# Interface.net
KiCad netlist of a schematic drawn in Altium Designer
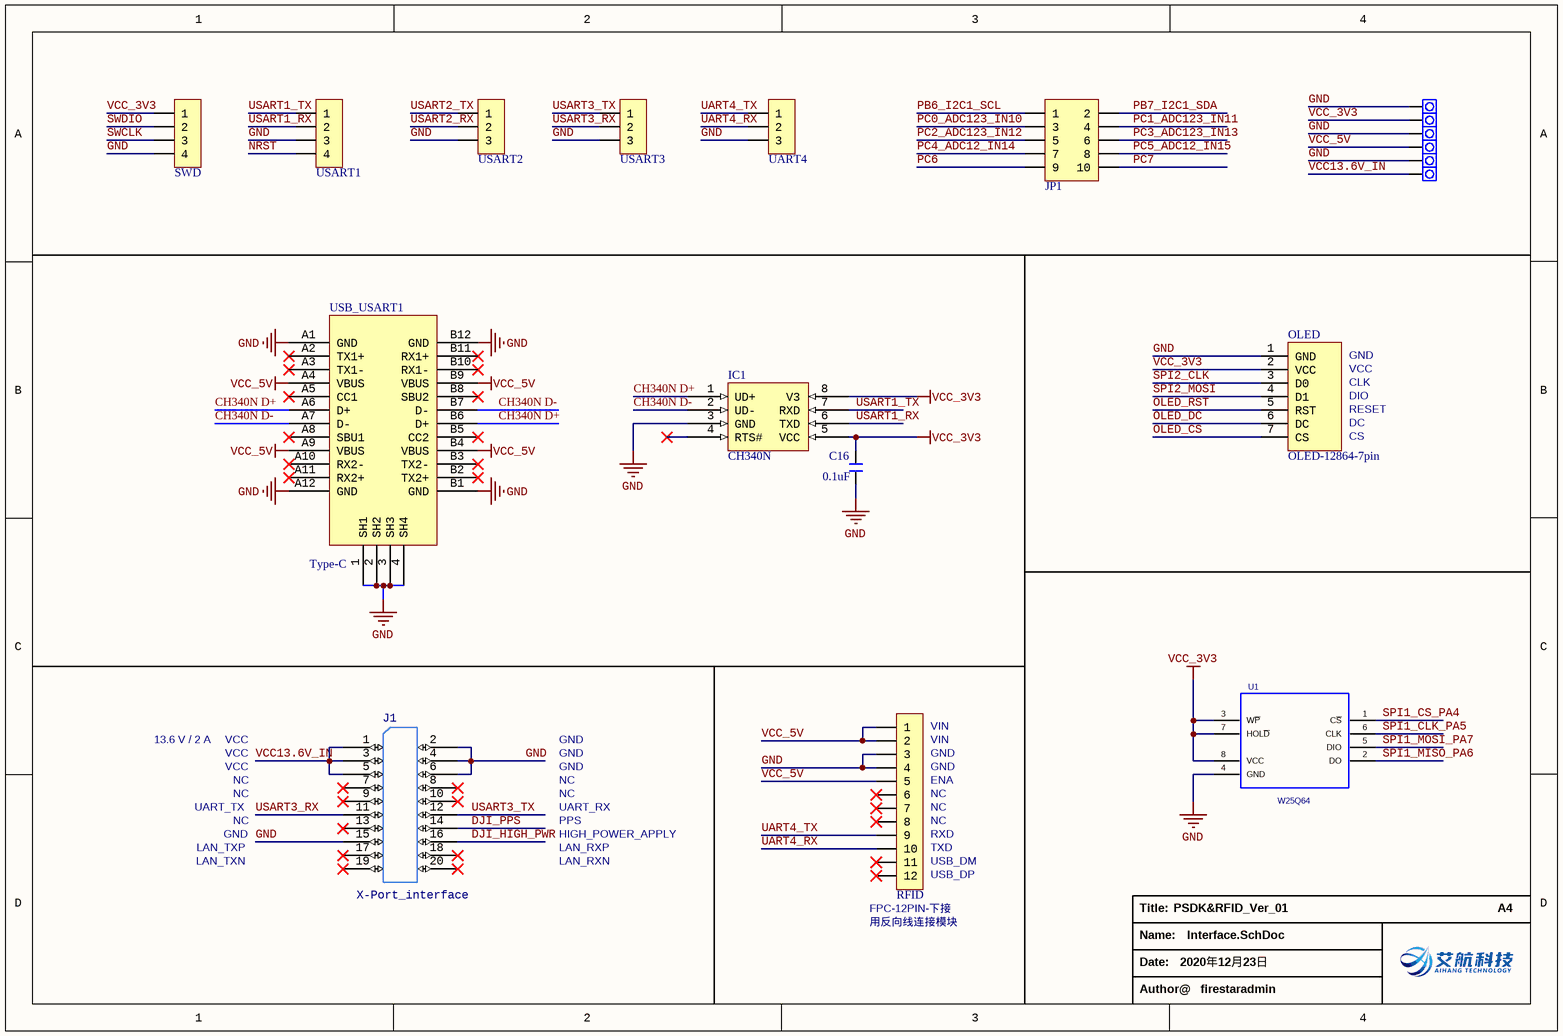
[diagram p0: Interface.SchDoc]

(export (version "E")
  (design (tool "Eeschema 10.0.6"))
  (components
    (comp (ref "C16")
      (value "0.1uF")
      (footprint "C 0603_L")
      (description "无极性贴片电容")
      (fields (field (name "版权归属") "源创客"))
      (libsource (lib "altium-import") (part "root_1_C_"))
    )
    (comp (ref "H1")
      (value "PAD")
      (footprint "PAD2-2.54")
      (description "引线焊盘")
      (fields (field (name "版权归属") "源创客"))
      (libsource (lib "SCH- 未分类器件") (part "PAD2"))
    )
    (comp (ref "H2")
      (value "PAD")
      (footprint "PAD2-2.54")
      (description "引线焊盘")
      (fields (field (name "版权归属") "源创客"))
      (libsource (lib "SCH- 未分类器件") (part "PAD2"))
    )
    (comp (ref "H3")
      (value "PAD")
      (footprint "PAD2-2.54")
      (description "引线焊盘")
      (fields (field (name "版权归属") "源创客"))
      (libsource (lib "SCH- 未分类器件") (part "PAD2"))
    )
    (comp (ref "IC1")
      (value "CH340N")
      (footprint "SOP8_N")
      (description "USB 转串口芯片 CH330/CH340N")
      (libsource (lib "altium-import") (part "root_0_CH340N_"))
    )
    (comp (ref "J1")
      (value "X-Port_interface")
      (footprint "s-50419-020xx-001")
      (description "20Pin-1.0MM-板对线连接器母座-WTB Wafer Conn.SMT D/R S/T Type.")
      (libsource (lib "SCH-板对线连接器-脚距1.0mm") (part "s-50419-020xx-001"))
    )
    (comp (ref "JP1")
      (value "Header 5X2")
      (footprint "HDR2.54-LI-2x5P")
      (description "5*2P接插件")
      (fields (field (name "版权归属") "源创客"))
      (libsource (lib "SCH-接插件-脚距2.54") (part "Header 5X2"))
    )
    (comp (ref "OLED")
      (value "OLED-12864-7pin")
      (footprint "OLED 0.96-7Pin")
      (description "OLED显示屏12864液晶屏串口oled模块ssd1306 12864OLED屏")
      (fields (field (name "版权归属") "源创客"))
      (libsource (lib "SCH-显示器件") (part "OLED-7pin-128x64-模组"))
    )
    (comp (ref "RFID")
      (value "FPC1.0-12P")
      (footprint "FPC1.0-2H-WS-12P")
      (description "FPC连接器")
      (fields (field (name "版权归属") "源创客"))
      (libsource (lib "SCH- FPC连接器") (part "FPC-12P"))
    )
    (comp (ref "SWD")
      (value "HDR-1X4")
      (footprint "HDR2.54-LI-4P")
      (description "4P接插件")
      (fields (field (name "版权归属") "源创客"))
      (libsource (lib "SCH-接插件-脚距2.54") (part "Header 4"))
    )
    (comp (ref "U1")
      (value "W25Q64")
      (footprint "SOP8W_L")
      (libsource (lib "altium-import") (part "root_0_W25Q64_"))
    )
    (comp (ref "UART4")
      (value "HDR-1X4")
      (footprint "HDR2.54-LI-3P")
      (description "3P接插件")
      (fields (field (name "版权归属") "源创客"))
      (libsource (lib "SCH-接插件-脚距2.54") (part "Header 3"))
    )
    (comp (ref "USART1")
      (value "HDR-1X4")
      (footprint "HDR2.54-LI-4P")
      (description "4P接插件")
      (fields (field (name "版权归属") "源创客"))
      (libsource (lib "SCH-接插件-脚距2.54") (part "Header 4"))
    )
    (comp (ref "USART2")
      (value "HDR-1X4")
      (footprint "HDR2.54-LI-3P")
      (description "3P接插件")
      (fields (field (name "版权归属") "源创客"))
      (libsource (lib "SCH-接插件-脚距2.54") (part "Header 3"))
    )
    (comp (ref "USART3")
      (value "HDR-1X4")
      (footprint "HDR2.54-LI-3P")
      (description "3P接插件")
      (fields (field (name "版权归属") "源创客"))
      (libsource (lib "SCH-接插件-脚距2.54") (part "Header 3"))
    )
    (comp (ref "USB_USART1")
      (value "Type-C")
      (footprint "Type-C")
      (libsource (lib "altium-import") (part "root_0_Type-C_"))
    )
  )
  (nets
    (net (code "2") (name "/CH340N D+") (class "Default")
      (node (ref "IC1") (pin "1") (pinfunction "UD+_1") (pintype "input"))
      (node (ref "USB_USART1") (pin "A6") (pinfunction "D+_A6") (pintype "passive"))
      (node (ref "USB_USART1") (pin "B6") (pinfunction "D+_B6") (pintype "passive"))
    )
    (net (code "3") (name "/CH340N D-") (class "Default")
      (node (ref "IC1") (pin "2") (pinfunction "UD-_2") (pintype "input"))
      (node (ref "USB_USART1") (pin "A7") (pinfunction "D-_A7") (pintype "passive"))
      (node (ref "USB_USART1") (pin "B7") (pinfunction "D-_B7") (pintype "passive"))
    )
    (net (code "4") (name "/DJI_HIGH_PWR") (class "Default")
      (node (ref "J1") (pin "16") (pintype "bidirectional"))
    )
    (net (code "5") (name "/DJI_PPS") (class "Default")
      (node (ref "J1") (pin "14") (pintype "bidirectional"))
    )
    (net (code "6") (name "/NRST") (class "Default")
      (node (ref "USART1") (pin "4") (pinfunction "4_4") (pintype "passive"))
    )
    (net (code "7") (name "/OLED_CS") (class "Default")
      (node (ref "OLED") (pin "7") (pinfunction "CS_7") (pintype "passive"))
    )
    (net (code "8") (name "/OLED_DC") (class "Default")
      (node (ref "OLED") (pin "6") (pinfunction "DC_6") (pintype "passive"))
    )
    (net (code "9") (name "/OLED_RST") (class "Default")
      (node (ref "OLED") (pin "5") (pinfunction "RST_5") (pintype "passive"))
    )
    (net (code "10") (name "/PB6_I2C1_SCL") (class "Default")
      (node (ref "JP1") (pin "1") (pinfunction "1_1") (pintype "passive"))
    )
    (net (code "11") (name "/PB7_I2C1_SDA") (class "Default")
      (node (ref "JP1") (pin "2") (pinfunction "2_2") (pintype "passive"))
    )
    (net (code "12") (name "/PC0_ADC123_IN10") (class "Default")
      (node (ref "JP1") (pin "3") (pinfunction "3_3") (pintype "passive"))
    )
    (net (code "13") (name "/PC1_ADC123_IN11") (class "Default")
      (node (ref "JP1") (pin "4") (pinfunction "4_4") (pintype "passive"))
    )
    (net (code "14") (name "/PC2_ADC123_IN12") (class "Default")
      (node (ref "JP1") (pin "5") (pinfunction "5_5") (pintype "passive"))
    )
    (net (code "15") (name "/PC3_ADC123_IN13") (class "Default")
      (node (ref "JP1") (pin "6") (pinfunction "6_6") (pintype "passive"))
    )
    (net (code "16") (name "/PC4_ADC12_IN14") (class "Default")
      (node (ref "JP1") (pin "7") (pinfunction "7_7") (pintype "passive"))
    )
    (net (code "17") (name "/PC5_ADC12_IN15") (class "Default")
      (node (ref "JP1") (pin "8") (pinfunction "8_8") (pintype "passive"))
    )
    (net (code "18") (name "/PC6") (class "Default")
      (node (ref "JP1") (pin "9") (pinfunction "9_9") (pintype "passive"))
    )
    (net (code "19") (name "/PC7") (class "Default")
      (node (ref "JP1") (pin "10") (pinfunction "10_10") (pintype "passive"))
    )
    (net (code "20") (name "/SPI1_CLK_PA5") (class "Default")
      (node (ref "U1") (pin "6") (pinfunction "CLK_6") (pintype "passive"))
    )
    (net (code "21") (name "/SPI1_CS_PA4") (class "Default")
      (node (ref "U1") (pin "1") (pinfunction "C~{S}_1") (pintype "passive"))
    )
    (net (code "22") (name "/SPI1_MISO_PA6") (class "Default")
      (node (ref "U1") (pin "2") (pinfunction "DO_2") (pintype "passive"))
    )
    (net (code "23") (name "/SPI1_MOSI_PA7") (class "Default")
      (node (ref "U1") (pin "5") (pinfunction "DIO_5") (pintype "passive"))
    )
    (net (code "24") (name "/SPI2_CLK") (class "Default")
      (node (ref "OLED") (pin "3") (pinfunction "D0_3") (pintype "passive"))
    )
    (net (code "25") (name "/SPI2_MOSI") (class "Default")
      (node (ref "OLED") (pin "4") (pinfunction "D1_4") (pintype "passive"))
    )
    (net (code "26") (name "/SWCLK") (class "Default")
      (node (ref "SWD") (pin "3") (pinfunction "3_3") (pintype "passive"))
    )
    (net (code "27") (name "/SWDIO") (class "Default")
      (node (ref "SWD") (pin "2") (pinfunction "2_2") (pintype "passive"))
    )
    (net (code "28") (name "/UART4_RX") (class "Default")
      (node (ref "RFID") (pin "10") (pinfunction "10_10") (pintype "passive"))
      (node (ref "UART4") (pin "2") (pinfunction "2_2") (pintype "passive"))
    )
    (net (code "29") (name "/UART4_TX") (class "Default")
      (node (ref "RFID") (pin "9") (pinfunction "9_9") (pintype "passive"))
      (node (ref "UART4") (pin "1") (pinfunction "1_1") (pintype "passive"))
    )
    (net (code "30") (name "/USART1_RX") (class "Default")
      (node (ref "IC1") (pin "6") (pinfunction "TXD_6") (pintype "input"))
      (node (ref "USART1") (pin "2") (pinfunction "2_2") (pintype "passive"))
    )
    (net (code "31") (name "/USART1_TX") (class "Default")
      (node (ref "IC1") (pin "7") (pinfunction "RXD_7") (pintype "input"))
      (node (ref "USART1") (pin "1") (pinfunction "1_1") (pintype "passive"))
    )
    (net (code "32") (name "/USART2_RX") (class "Default")
      (node (ref "USART2") (pin "2") (pinfunction "2_2") (pintype "passive"))
    )
    (net (code "33") (name "/USART2_TX") (class "Default")
      (node (ref "USART2") (pin "1") (pinfunction "1_1") (pintype "passive"))
    )
    (net (code "34") (name "/USART3_RX") (class "Default")
      (node (ref "J1") (pin "11") (pintype "bidirectional"))
      (node (ref "USART3") (pin "2") (pinfunction "2_2") (pintype "passive"))
    )
    (net (code "35") (name "/USART3_TX") (class "Default")
      (node (ref "J1") (pin "12") (pintype "bidirectional"))
      (node (ref "USART3") (pin "1") (pinfunction "1_1") (pintype "passive"))
    )
    (net (code "36") (name "/VCC13.6V_IN") (class "Default")
      (node (ref "H3") (pin "2") (pinfunction "2_2") (pintype "passive"))
      (node (ref "J1") (pin "1") (pintype "bidirectional"))
      (node (ref "J1") (pin "3") (pintype "bidirectional"))
      (node (ref "J1") (pin "5") (pintype "bidirectional"))
    )
    (net (code "37") (name "GND") (class "Default")
      (node (ref "C16") (pin "1") (pinfunction "1_1") (pintype "passive"))
      (node (ref "H1") (pin "1") (pinfunction "1_1") (pintype "passive"))
      (node (ref "H2") (pin "1") (pinfunction "1_1") (pintype "passive"))
      (node (ref "H3") (pin "1") (pinfunction "1_1") (pintype "passive"))
      (node (ref "IC1") (pin "3") (pinfunction "GND_3") (pintype "input"))
      (node (ref "J1") (pin "15") (pintype "bidirectional"))
      (node (ref "J1") (pin "2") (pintype "bidirectional"))
      (node (ref "J1") (pin "4") (pintype "bidirectional"))
      (node (ref "J1") (pin "6") (pintype "bidirectional"))
      (node (ref "OLED") (pin "1") (pinfunction "GND_1") (pintype "passive"))
      (node (ref "RFID") (pin "3") (pinfunction "3_3") (pintype "passive"))
      (node (ref "RFID") (pin "4") (pinfunction "4_4") (pintype "passive"))
      (node (ref "SWD") (pin "4") (pinfunction "4_4") (pintype "passive"))
      (node (ref "U1") (pin "4") (pinfunction "GND_4") (pintype "passive"))
      (node (ref "UART4") (pin "3") (pinfunction "3_3") (pintype "passive"))
      (node (ref "USART1") (pin "3") (pinfunction "3_3") (pintype "passive"))
      (node (ref "USART2") (pin "3") (pinfunction "3_3") (pintype "passive"))
      (node (ref "USART3") (pin "3") (pinfunction "3_3") (pintype "passive"))
      (node (ref "USB_USART1") (pin "1") (pinfunction "SH1_1") (pintype "passive"))
      (node (ref "USB_USART1") (pin "2") (pinfunction "SH2_2") (pintype "passive"))
      (node (ref "USB_USART1") (pin "3") (pinfunction "SH3_3") (pintype "passive"))
      (node (ref "USB_USART1") (pin "4") (pinfunction "SH4_4") (pintype "passive"))
      (node (ref "USB_USART1") (pin "A1") (pinfunction "GND_A1") (pintype "passive"))
      (node (ref "USB_USART1") (pin "A12") (pinfunction "GND_A12") (pintype "passive"))
      (node (ref "USB_USART1") (pin "B1") (pinfunction "GND_B1") (pintype "passive"))
      (node (ref "USB_USART1") (pin "B12") (pinfunction "GND_B12") (pintype "passive"))
    )
    (net (code "38") (name "VCC_3V3") (class "Default")
      (node (ref "C16") (pin "2") (pinfunction "2_2") (pintype "passive"))
      (node (ref "H1") (pin "2") (pinfunction "2_2") (pintype "passive"))
      (node (ref "IC1") (pin "5") (pinfunction "VCC_5") (pintype "input"))
      (node (ref "IC1") (pin "8") (pinfunction "V3_8") (pintype "input"))
      (node (ref "OLED") (pin "2") (pinfunction "VCC_2") (pintype "passive"))
      (node (ref "SWD") (pin "1") (pinfunction "1_1") (pintype "passive"))
      (node (ref "U1") (pin "3") (pinfunction "W~{P}_3") (pintype "passive"))
      (node (ref "U1") (pin "7") (pinfunction "HOL~{D}_7") (pintype "passive"))
      (node (ref "U1") (pin "8") (pinfunction "VCC_8") (pintype "passive"))
    )
    (net (code "39") (name "VCC_5V") (class "Default")
      (node (ref "H2") (pin "2") (pinfunction "2_2") (pintype "passive"))
      (node (ref "RFID") (pin "1") (pinfunction "1_1") (pintype "passive"))
      (node (ref "RFID") (pin "2") (pinfunction "2_2") (pintype "passive"))
      (node (ref "RFID") (pin "5") (pinfunction "5_5") (pintype "passive"))
      (node (ref "USB_USART1") (pin "A4") (pinfunction "VBUS_A4") (pintype "passive"))
      (node (ref "USB_USART1") (pin "A9") (pinfunction "VBUS_A9") (pintype "passive"))
      (node (ref "USB_USART1") (pin "B4") (pinfunction "VBUS_B4") (pintype "passive"))
      (node (ref "USB_USART1") (pin "B9") (pinfunction "VBUS_B9") (pintype "passive"))
    )
    (net (code "40") (name "unconnected-(IC1-RTS#-Pad4)") (class "Default")
      (node (ref "IC1") (pin "4") (pinfunction "RTS#_4") (pintype "input+no_connect"))
    )
    (net (code "41") (name "unconnected-(J1-Pad7)") (class "Default")
      (node (ref "J1") (pin "7") (pintype "bidirectional+no_connect"))
    )
    (net (code "42") (name "unconnected-(J1-Pad8)") (class "Default")
      (node (ref "J1") (pin "8") (pintype "bidirectional+no_connect"))
    )
    (net (code "43") (name "unconnected-(J1-Pad9)") (class "Default")
      (node (ref "J1") (pin "9") (pintype "bidirectional+no_connect"))
    )
    (net (code "44") (name "unconnected-(J1-Pad10)") (class "Default")
      (node (ref "J1") (pin "10") (pintype "bidirectional+no_connect"))
    )
    (net (code "45") (name "unconnected-(J1-Pad13)") (class "Default")
      (node (ref "J1") (pin "13") (pintype "bidirectional+no_connect"))
    )
    (net (code "46") (name "unconnected-(J1-Pad17)") (class "Default")
      (node (ref "J1") (pin "17") (pintype "bidirectional+no_connect"))
    )
    (net (code "47") (name "unconnected-(J1-Pad18)") (class "Default")
      (node (ref "J1") (pin "18") (pintype "bidirectional+no_connect"))
    )
    (net (code "48") (name "unconnected-(J1-Pad19)") (class "Default")
      (node (ref "J1") (pin "19") (pintype "bidirectional+no_connect"))
    )
    (net (code "49") (name "unconnected-(J1-Pad20)") (class "Default")
      (node (ref "J1") (pin "20") (pintype "bidirectional+no_connect"))
    )
    (net (code "50") (name "unconnected-(RFID-Pad6)") (class "Default")
      (node (ref "RFID") (pin "6") (pinfunction "6_6") (pintype "passive+no_connect"))
    )
    (net (code "51") (name "unconnected-(RFID-Pad7)") (class "Default")
      (node (ref "RFID") (pin "7") (pinfunction "7_7") (pintype "passive+no_connect"))
    )
    (net (code "52") (name "unconnected-(RFID-Pad8)") (class "Default")
      (node (ref "RFID") (pin "8") (pinfunction "8_8") (pintype "passive+no_connect"))
    )
    (net (code "53") (name "unconnected-(RFID-Pad11)") (class "Default")
      (node (ref "RFID") (pin "11") (pinfunction "11_11") (pintype "passive+no_connect"))
    )
    (net (code "54") (name "unconnected-(RFID-Pad12)") (class "Default")
      (node (ref "RFID") (pin "12") (pinfunction "12_12") (pintype "passive+no_connect"))
    )
    (net (code "55") (name "unconnected-(USB_USART1-CC1-PadA5)") (class "Default")
      (node (ref "USB_USART1") (pin "A5") (pinfunction "CC1_A5") (pintype "passive+no_connect"))
    )
    (net (code "56") (name "unconnected-(USB_USART1-CC2-PadB5)") (class "Default")
      (node (ref "USB_USART1") (pin "B5") (pinfunction "CC2_B5") (pintype "passive+no_connect"))
    )
    (net (code "57") (name "unconnected-(USB_USART1-RX1+-PadB11)") (class "Default")
      (node (ref "USB_USART1") (pin "B11") (pinfunction "RX1+_B11") (pintype "passive+no_connect"))
    )
    (net (code "58") (name "unconnected-(USB_USART1-RX1--PadB10)") (class "Default")
      (node (ref "USB_USART1") (pin "B10") (pinfunction "RX1-_B10") (pintype "passive+no_connect"))
    )
    (net (code "59") (name "unconnected-(USB_USART1-RX2+-PadA11)") (class "Default")
      (node (ref "USB_USART1") (pin "A11") (pinfunction "RX2+_A11") (pintype "passive+no_connect"))
    )
    (net (code "60") (name "unconnected-(USB_USART1-RX2--PadA10)") (class "Default")
      (node (ref "USB_USART1") (pin "A10") (pinfunction "RX2-_A10") (pintype "passive+no_connect"))
    )
    (net (code "61") (name "unconnected-(USB_USART1-SBU1-PadA8)") (class "Default")
      (node (ref "USB_USART1") (pin "A8") (pinfunction "SBU1_A8") (pintype "passive+no_connect"))
    )
    (net (code "62") (name "unconnected-(USB_USART1-SBU2-PadB8)") (class "Default")
      (node (ref "USB_USART1") (pin "B8") (pinfunction "SBU2_B8") (pintype "passive+no_connect"))
    )
    (net (code "63") (name "unconnected-(USB_USART1-TX1+-PadA2)") (class "Default")
      (node (ref "USB_USART1") (pin "A2") (pinfunction "TX1+_A2") (pintype "passive+no_connect"))
    )
    (net (code "64") (name "unconnected-(USB_USART1-TX1--PadA3)") (class "Default")
      (node (ref "USB_USART1") (pin "A3") (pinfunction "TX1-_A3") (pintype "passive+no_connect"))
    )
    (net (code "65") (name "unconnected-(USB_USART1-TX2+-PadB2)") (class "Default")
      (node (ref "USB_USART1") (pin "B2") (pinfunction "TX2+_B2") (pintype "passive+no_connect"))
    )
    (net (code "66") (name "unconnected-(USB_USART1-TX2--PadB3)") (class "Default")
      (node (ref "USB_USART1") (pin "B3") (pinfunction "TX2-_B3") (pintype "passive+no_connect"))
    )
  )
)
